# ADC.net
KiCad netlist of a schematic drawn in Altium Designer
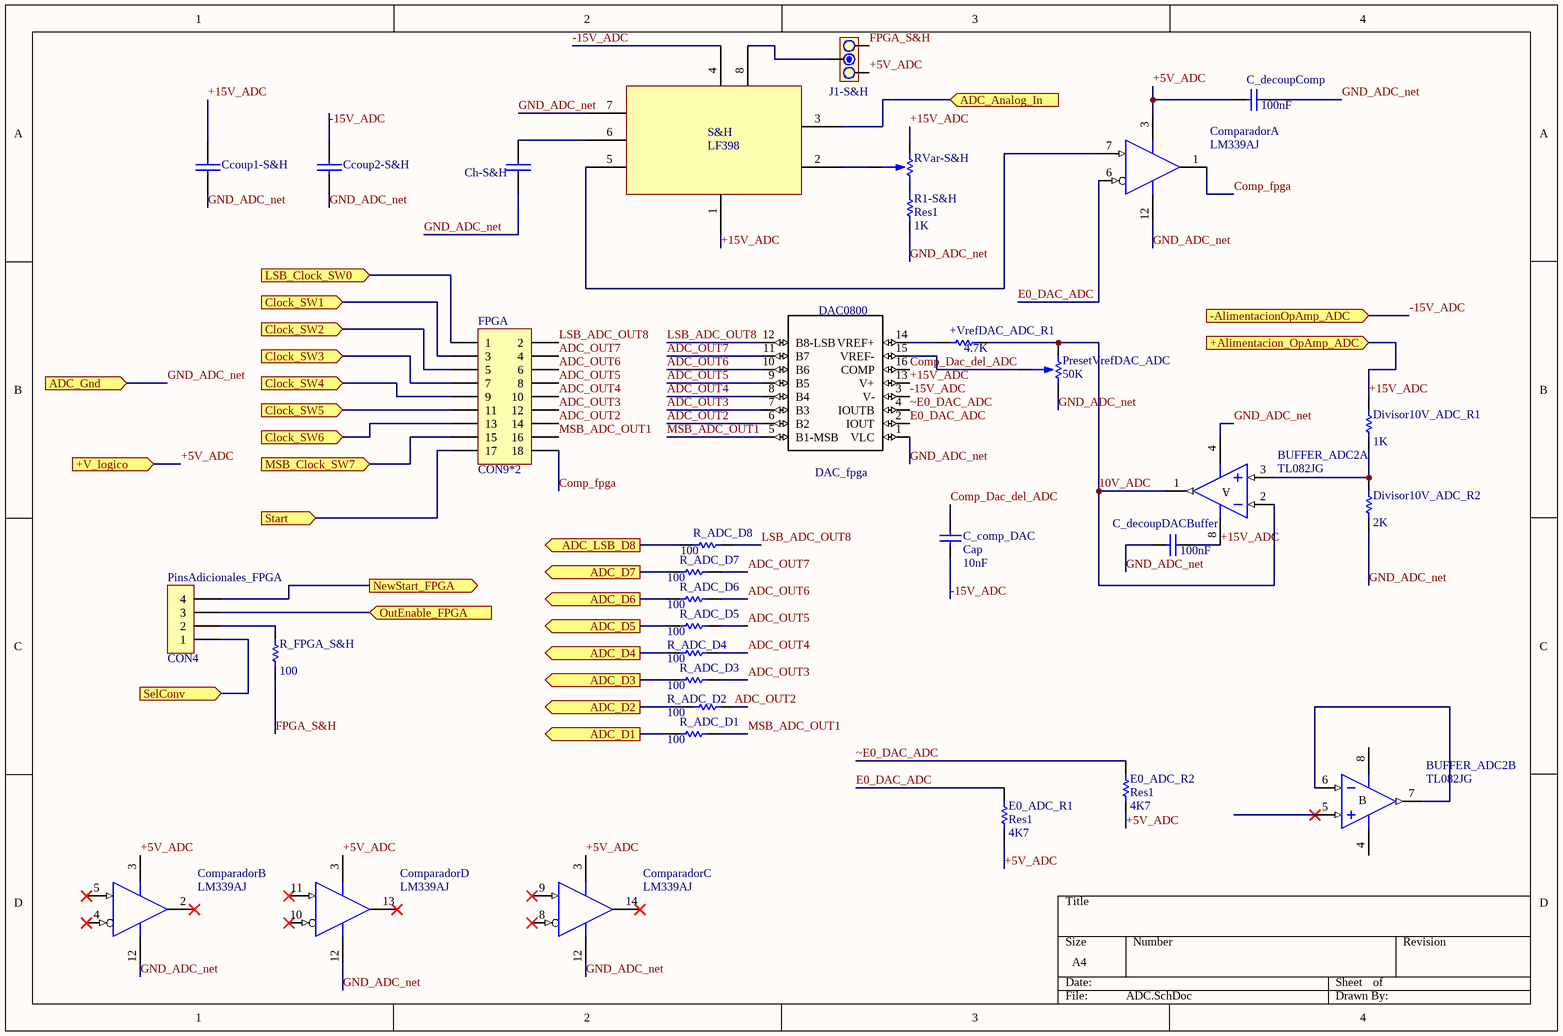
[diagram p0: ADC.SchDoc]

(export (version "E")
  (design (tool "Eeschema 10.0.6"))
  (components
    (comp (ref "+VrefDAC_ADC_R1")
      (value "4.7K")
      (footprint "AXIAL-0.3")
      (description "Resistor")
      (fields (field (name "Comment") "Res1") (field (name "PUBLISHER") "Altium Limited"))
      (libsource (lib "Miscellaneous Devices") (part "Res1"))
    )
    (comp (ref "BUFFER_ADC2")
      (value "TL082JG")
      (footprint "JG008")
      (description "JFET-Input Operational Amplifier")
      (fields (field (name "PUBLISHER") "Altium Limited"))
      (libsource (lib "TI Operational Amplifier") (part "TL082JG"))
    )
    (comp (ref "Ccoup1-S&H") (value "CAP") (footprint "CAP200") (libsource (lib "LIBEBAL") (part "CAP")))
    (comp (ref "Ccoup2-S&H") (value "CAP") (footprint "CAP200") (libsource (lib "LIBEBAL") (part "CAP")))
    (comp (ref "Ch-S&H") (value "CAP") (footprint "CAP200") (libsource (lib "LIBEBAL") (part "CAP")))
    (comp (ref "Comparador")
      (value "LM339AJ")
      (footprint "J014")
      (description "Quad Differential Comparator")
      (fields (field (name "PUBLISHER") "Altium Limited"))
      (libsource (lib "TI Analog Comparator") (part "LM339AJ"))
    )
    (comp (ref "C_comp_DAC")
      (value "Cap")
      (footprint "RAD-0.3")
      (description "Capacitor")
      (fields (field (name "ALTIUM_VALUE") "10nF") (field (name "PUBLISHER") "Altium Limited"))
      (libsource (lib "Miscellaneous Devices") (part "Cap"))
    )
    (comp (ref "C_decoupComp")
      (value "100nF")
      (footprint "RAD-0.3")
      (description "Capacitor")
      (fields (field (name "Comment") "Cap") (field (name "PUBLISHER") "Altium Limited"))
      (libsource (lib "Miscellaneous Devices") (part "Cap"))
    )
    (comp (ref "C_decoupDACBuffer")
      (value "100nF")
      (footprint "RAD-0.3")
      (description "Capacitor")
      (fields (field (name "Comment") "Cap") (field (name "PUBLISHER") "Altium Limited"))
      (libsource (lib "Miscellaneous Devices") (part "Cap"))
    )
    (comp (ref "DAC_fpga")
      (value "DAC0800")
      (footprint "*DIL16")
      (fields
        (field (name "MF") "Texas Instruments")
        (field (name "DIGI-KEY_PART_NUMBER") "DAC0800LCN/NOPB-ND")
      )
      (libsource (lib "DAC0800") (part "DAC0800"))
    )
    (comp (ref "Divisor10V_ADC_R1")
      (value "1K")
      (footprint "AXIAL-0.3")
      (description "Resistor")
      (fields (field (name "Comment") "Res1") (field (name "PUBLISHER") "Altium Limited"))
      (libsource (lib "Miscellaneous Devices") (part "Res1"))
    )
    (comp (ref "Divisor10V_ADC_R2")
      (value "2K")
      (footprint "AXIAL-0.3")
      (description "Resistor")
      (fields (field (name "Comment") "Res1") (field (name "PUBLISHER") "Altium Limited"))
      (libsource (lib "Miscellaneous Devices") (part "Res1"))
    )
    (comp (ref "E0_ADC_R1")
      (value "Res1")
      (footprint "AXIAL-0.3")
      (description "Resistor")
      (fields (field (name "ALTIUM_VALUE") "4K7") (field (name "PUBLISHER") "Altium Limited"))
      (libsource (lib "Miscellaneous Devices") (part "Res1"))
    )
    (comp (ref "E0_ADC_R2")
      (value "Res1")
      (footprint "AXIAL-0.3")
      (description "Resistor")
      (fields (field (name "ALTIUM_VALUE") "4K7") (field (name "PUBLISHER") "Altium Limited"))
      (libsource (lib "Miscellaneous Devices") (part "Res1"))
    )
    (comp (ref "FPGA") (value "CON9*2") (footprint "SIP9*2") (libsource (lib "LIBEBAL") (part "CON9*2")))
    (comp (ref "J1-S&H") (value "JUMPER") (footprint "JUMPER3") (libsource (lib "LIBEBAL") (part "JUMPER3")))
    (comp (ref "PinsAdicionales_FPGA")
      (value "CON4")
      (footprint "SIP4")
      (libsource (lib "LIBEBAL") (part "CON4"))
    )
    (comp (ref "PresetVrefDAC_ADC")
      (value "50K")
      (footprint "PRESET V")
      (libsource (lib "LIBEBAL") (part "PRESET"))
    )
    (comp (ref "R1-S&H")
      (value "Res1")
      (footprint "AXIAL-0.3")
      (description "Resistor")
      (fields (field (name "ALTIUM_VALUE") "1K") (field (name "PUBLISHER") "Altium Limited"))
      (libsource (lib "Miscellaneous Devices") (part "Res1"))
    )
    (comp (ref "RVar-S&H")
      (value "PRESET")
      (footprint "PRESET V")
      (libsource (lib "LIBEBAL") (part "PRESET"))
    )
    (comp (ref "R_ADC_D1")
      (value "100")
      (footprint "AXIAL-0.3")
      (description "Resistor")
      (fields (field (name "Comment") "Res1") (field (name "PUBLISHER") "Altium Limited"))
      (libsource (lib "Miscellaneous Devices") (part "Res1"))
    )
    (comp (ref "R_ADC_D2")
      (value "100")
      (footprint "AXIAL-0.3")
      (description "Resistor")
      (fields (field (name "Comment") "Res1") (field (name "PUBLISHER") "Altium Limited"))
      (libsource (lib "Miscellaneous Devices") (part "Res1"))
    )
    (comp (ref "R_ADC_D3")
      (value "100")
      (footprint "AXIAL-0.3")
      (description "Resistor")
      (fields (field (name "Comment") "Res1") (field (name "PUBLISHER") "Altium Limited"))
      (libsource (lib "Miscellaneous Devices") (part "Res1"))
    )
    (comp (ref "R_ADC_D4")
      (value "100")
      (footprint "AXIAL-0.3")
      (description "Resistor")
      (fields (field (name "Comment") "Res1") (field (name "PUBLISHER") "Altium Limited"))
      (libsource (lib "Miscellaneous Devices") (part "Res1"))
    )
    (comp (ref "R_ADC_D5")
      (value "100")
      (footprint "AXIAL-0.3")
      (description "Resistor")
      (fields (field (name "Comment") "Res1") (field (name "PUBLISHER") "Altium Limited"))
      (libsource (lib "Miscellaneous Devices") (part "Res1"))
    )
    (comp (ref "R_ADC_D6")
      (value "100")
      (footprint "AXIAL-0.3")
      (description "Resistor")
      (fields (field (name "Comment") "Res1") (field (name "PUBLISHER") "Altium Limited"))
      (libsource (lib "Miscellaneous Devices") (part "Res1"))
    )
    (comp (ref "R_ADC_D7")
      (value "100")
      (footprint "AXIAL-0.3")
      (description "Resistor")
      (fields (field (name "Comment") "Res1") (field (name "PUBLISHER") "Altium Limited"))
      (libsource (lib "Miscellaneous Devices") (part "Res1"))
    )
    (comp (ref "R_ADC_D8")
      (value "100")
      (footprint "AXIAL-0.3")
      (description "Resistor")
      (fields (field (name "Comment") "Res1") (field (name "PUBLISHER") "Altium Limited"))
      (libsource (lib "Miscellaneous Devices") (part "Res1"))
    )
    (comp (ref "R_FPGA_S&H")
      (value "100")
      (footprint "AXIAL-0.3")
      (description "Resistor")
      (fields (field (name "Comment") "Res1") (field (name "PUBLISHER") "Altium Limited"))
      (libsource (lib "Miscellaneous Devices") (part "Res1"))
    )
    (comp (ref "S&H")
      (value "LF398")
      (footprint "DIP8")
      (description "Sample and Hold Amplifier")
      (libsource (lib "LIBEBAL") (part "LM555"))
    )
  )
  (nets
    (net (code "1") (name "/+5V_ADC") (class "Default")
      (node (ref "C_decoupComp") (pin "1") (pinfunction "1_1") (pintype "passive"))
      (node (ref "Comparador") (pin "3") (pinfunction "VCC_3") (pintype "power_in"))
      (node (ref "E0_ADC_R1") (pin "1") (pinfunction "1_1") (pintype "passive"))
      (node (ref "E0_ADC_R2") (pin "1") (pinfunction "1_1") (pintype "passive"))
      (node (ref "J1-S&H") (pin "3") (pinfunction "3_3") (pintype "passive"))
    )
    (net (code "2") (name "/+15V_ADC") (class "Default")
      (node (ref "BUFFER_ADC2") (pin "8") (pinfunction "V+_8") (pintype "power_in"))
      (node (ref "C_decoupDACBuffer") (pin "2") (pinfunction "2_2") (pintype "passive"))
      (node (ref "Ccoup1-S&H") (pin "1") (pinfunction "1_1") (pintype "passive"))
      (node (ref "DAC_fpga") (pin "13") (pinfunction "V+_13") (pintype "bidirectional"))
      (node (ref "Divisor10V_ADC_R1") (pin "2") (pinfunction "2_2") (pintype "passive"))
      (node (ref "RVar-S&H") (pin "3") (pinfunction "3_3") (pintype "passive"))
      (node (ref "S&H") (pin "1") (pinfunction "GND_1") (pintype "passive"))
    )
    (net (code "3") (name "/-15V_ADC") (class "Default")
      (node (ref "C_comp_DAC") (pin "1") (pinfunction "1_1") (pintype "passive"))
      (node (ref "Ccoup2-S&H") (pin "1") (pinfunction "1_1") (pintype "passive"))
      (node (ref "DAC_fpga") (pin "3") (pinfunction "V-_3") (pintype "bidirectional"))
      (node (ref "S&H") (pin "4") (pinfunction "RESET_4") (pintype "passive"))
    )
    (net (code "4") (name "/10V_ADC") (class "Default")
      (node (ref "+VrefDAC_ADC_R1") (pin "2") (pinfunction "2_2") (pintype "passive"))
      (node (ref "BUFFER_ADC2") (pin "1") (pinfunction "OUT_1") (pintype "output"))
      (node (ref "BUFFER_ADC2") (pin "2") (pinfunction "IN-_2") (pintype "input"))
      (node (ref "PresetVrefDAC_ADC") (pin "3") (pinfunction "3_3") (pintype "passive"))
    )
    (net (code "5") (name "/ADC_Analog_In") (class "Default")
      (node (ref "S&H") (pin "3") (pinfunction "OUT_3") (pintype "passive"))
    )
    (net (code "6") (name "/ADC_D1") (class "Default")
      (node (ref "R_ADC_D1") (pin "1") (pinfunction "1_1") (pintype "passive"))
    )
    (net (code "7") (name "/ADC_D2") (class "Default")
      (node (ref "R_ADC_D2") (pin "1") (pinfunction "1_1") (pintype "passive"))
    )
    (net (code "8") (name "/ADC_D3") (class "Default")
      (node (ref "R_ADC_D3") (pin "1") (pinfunction "1_1") (pintype "passive"))
    )
    (net (code "9") (name "/ADC_D4") (class "Default")
      (node (ref "R_ADC_D4") (pin "1") (pinfunction "1_1") (pintype "passive"))
    )
    (net (code "10") (name "/ADC_D5") (class "Default")
      (node (ref "R_ADC_D5") (pin "1") (pinfunction "1_1") (pintype "passive"))
    )
    (net (code "11") (name "/ADC_D6") (class "Default")
      (node (ref "R_ADC_D6") (pin "1") (pinfunction "1_1") (pintype "passive"))
    )
    (net (code "12") (name "/ADC_D7") (class "Default")
      (node (ref "R_ADC_D7") (pin "1") (pinfunction "1_1") (pintype "passive"))
    )
    (net (code "13") (name "/ADC_LSB_D8") (class "Default")
      (node (ref "R_ADC_D8") (pin "1") (pinfunction "1_1") (pintype "passive"))
    )
    (net (code "14") (name "/ADC_OUT2") (class "Default")
      (node (ref "DAC_fpga") (pin "6") (pinfunction "B2_6") (pintype "bidirectional"))
      (node (ref "FPGA") (pin "14") (pinfunction "14_14") (pintype "passive"))
      (node (ref "R_ADC_D2") (pin "2") (pinfunction "2_2") (pintype "passive"))
    )
    (net (code "15") (name "/ADC_OUT3") (class "Default")
      (node (ref "DAC_fpga") (pin "7") (pinfunction "B3_7") (pintype "bidirectional"))
      (node (ref "FPGA") (pin "12") (pinfunction "12_12") (pintype "passive"))
      (node (ref "R_ADC_D3") (pin "2") (pinfunction "2_2") (pintype "passive"))
    )
    (net (code "16") (name "/ADC_OUT4") (class "Default")
      (node (ref "DAC_fpga") (pin "8") (pinfunction "B4_8") (pintype "bidirectional"))
      (node (ref "FPGA") (pin "10") (pinfunction "10_10") (pintype "passive"))
      (node (ref "R_ADC_D4") (pin "2") (pinfunction "2_2") (pintype "passive"))
    )
    (net (code "17") (name "/ADC_OUT5") (class "Default")
      (node (ref "DAC_fpga") (pin "9") (pinfunction "B5_9") (pintype "bidirectional"))
      (node (ref "FPGA") (pin "8") (pinfunction "8_8") (pintype "passive"))
      (node (ref "R_ADC_D5") (pin "2") (pinfunction "2_2") (pintype "passive"))
    )
    (net (code "18") (name "/ADC_OUT6") (class "Default")
      (node (ref "DAC_fpga") (pin "10") (pinfunction "B6_10") (pintype "bidirectional"))
      (node (ref "FPGA") (pin "6") (pinfunction "6_6") (pintype "passive"))
      (node (ref "R_ADC_D6") (pin "2") (pinfunction "2_2") (pintype "passive"))
    )
    (net (code "19") (name "/ADC_OUT7") (class "Default")
      (node (ref "DAC_fpga") (pin "11") (pinfunction "B7_11") (pintype "bidirectional"))
      (node (ref "FPGA") (pin "4") (pinfunction "4_4") (pintype "passive"))
      (node (ref "R_ADC_D7") (pin "2") (pinfunction "2_2") (pintype "passive"))
    )
    (net (code "20") (name "/Clock_SW1") (class "Default")
      (node (ref "FPGA") (pin "3") (pinfunction "3_3") (pintype "passive"))
    )
    (net (code "21") (name "/Clock_SW2") (class "Default")
      (node (ref "FPGA") (pin "5") (pinfunction "5_5") (pintype "passive"))
    )
    (net (code "22") (name "/Clock_SW3") (class "Default")
      (node (ref "FPGA") (pin "7") (pinfunction "7_7") (pintype "passive"))
    )
    (net (code "23") (name "/Clock_SW4") (class "Default")
      (node (ref "FPGA") (pin "9") (pinfunction "9_9") (pintype "passive"))
    )
    (net (code "24") (name "/Clock_SW5") (class "Default")
      (node (ref "FPGA") (pin "11") (pinfunction "11_11") (pintype "passive"))
    )
    (net (code "25") (name "/Clock_SW6") (class "Default")
      (node (ref "FPGA") (pin "13") (pinfunction "13_13") (pintype "passive"))
    )
    (net (code "26") (name "/Comp_Dac_del_ADC") (class "Default")
      (node (ref "C_comp_DAC") (pin "2") (pinfunction "2_2") (pintype "passive"))
      (node (ref "DAC_fpga") (pin "16") (pinfunction "COMP_16") (pintype "bidirectional"))
    )
    (net (code "27") (name "/Comp_fpga") (class "Default")
      (node (ref "Comparador") (pin "1") (pinfunction "OUT_1") (pintype "open_collector"))
      (node (ref "FPGA") (pin "18") (pinfunction "18_18") (pintype "passive"))
    )
    (net (code "28") (name "/E0_DAC_ADC") (class "Default")
      (node (ref "Comparador") (pin "6") (pinfunction "IN-_6") (pintype "input"))
      (node (ref "DAC_fpga") (pin "2") (pinfunction "IOUT_2") (pintype "bidirectional"))
      (node (ref "E0_ADC_R1") (pin "2") (pinfunction "2_2") (pintype "passive"))
    )
    (net (code "29") (name "/FPGA_S&H") (class "Default")
      (node (ref "J1-S&H") (pin "1") (pinfunction "1_1") (pintype "passive"))
      (node (ref "R_FPGA_S&H") (pin "1") (pinfunction "1_1") (pintype "passive"))
    )
    (net (code "30") (name "/GND_ADC_net") (class "Default")
      (node (ref "BUFFER_ADC2") (pin "4") (pinfunction "V-_4") (pintype "power_in"))
      (node (ref "C_decoupComp") (pin "2") (pinfunction "2_2") (pintype "passive"))
      (node (ref "C_decoupDACBuffer") (pin "1") (pinfunction "1_1") (pintype "passive"))
      (node (ref "Ccoup1-S&H") (pin "2") (pinfunction "2_2") (pintype "passive"))
      (node (ref "Ccoup2-S&H") (pin "2") (pinfunction "2_2") (pintype "passive"))
      (node (ref "Ch-S&H") (pin "2") (pinfunction "2_2") (pintype "passive"))
      (node (ref "Comparador") (pin "12") (pinfunction "GND_12") (pintype "power_in"))
      (node (ref "DAC_fpga") (pin "1") (pinfunction "VLC_1") (pintype "bidirectional"))
      (node (ref "Divisor10V_ADC_R2") (pin "1") (pinfunction "1_1") (pintype "passive"))
      (node (ref "PresetVrefDAC_ADC") (pin "1") (pinfunction "1_1") (pintype "passive"))
      (node (ref "R1-S&H") (pin "1") (pinfunction "1_1") (pintype "passive"))
      (node (ref "S&H") (pin "7") (pinfunction "DISCHARGE_7") (pintype "passive"))
    )
    (net (code "31") (name "/LSB_ADC_OUT8") (class "Default")
      (node (ref "DAC_fpga") (pin "12") (pinfunction "B8-LSB_12") (pintype "bidirectional"))
      (node (ref "FPGA") (pin "2") (pinfunction "2_2") (pintype "passive"))
      (node (ref "R_ADC_D8") (pin "2") (pinfunction "2_2") (pintype "passive"))
    )
    (net (code "32") (name "/LSB_Clock_SW0") (class "Default")
      (node (ref "FPGA") (pin "1") (pinfunction "1_1") (pintype "passive"))
    )
    (net (code "33") (name "/MSB_ADC_OUT1") (class "Default")
      (node (ref "DAC_fpga") (pin "5") (pinfunction "B1-MSB_5") (pintype "bidirectional"))
      (node (ref "FPGA") (pin "16") (pinfunction "16_16") (pintype "passive"))
      (node (ref "R_ADC_D1") (pin "2") (pinfunction "2_2") (pintype "passive"))
    )
    (net (code "34") (name "/MSB_Clock_SW7") (class "Default")
      (node (ref "FPGA") (pin "15") (pinfunction "15_15") (pintype "passive"))
    )
    (net (code "35") (name "/NewStart_FPGA") (class "Default")
      (node (ref "PinsAdicionales_FPGA") (pin "4") (pinfunction "4_4") (pintype "passive"))
    )
    (net (code "36") (name "/OutEnable_FPGA") (class "Default")
      (node (ref "PinsAdicionales_FPGA") (pin "3") (pinfunction "3_3") (pintype "passive"))
    )
    (net (code "37") (name "/SelConv") (class "Default")
      (node (ref "PinsAdicionales_FPGA") (pin "1") (pinfunction "1_1") (pintype "passive"))
    )
    (net (code "38") (name "/Start") (class "Default")
      (node (ref "FPGA") (pin "17") (pinfunction "17_17") (pintype "passive"))
    )
    (net (code "39") (name "/~E0_DAC_ADC") (class "Default")
      (node (ref "DAC_fpga") (pin "4") (pinfunction "IOUTB_4") (pintype "bidirectional"))
      (node (ref "E0_ADC_R2") (pin "2") (pinfunction "2_2") (pintype "passive"))
    )
    (net (code "40") (name "Net-(BUFFER_ADC2A-IN+)") (class "Default")
      (node (ref "BUFFER_ADC2") (pin "3") (pinfunction "IN+_3") (pintype "input"))
      (node (ref "Divisor10V_ADC_R1") (pin "1") (pinfunction "1_1") (pintype "passive"))
      (node (ref "Divisor10V_ADC_R2") (pin "2") (pinfunction "2_2") (pintype "passive"))
    )
    (net (code "41") (name "Net-(BUFFER_ADC2B-IN-)") (class "Default")
      (node (ref "BUFFER_ADC2") (pin "6") (pinfunction "IN-_6") (pintype "input"))
      (node (ref "BUFFER_ADC2") (pin "7") (pinfunction "OUT_7") (pintype "output"))
    )
    (net (code "42") (name "Net-(ComparadorA-IN+)") (class "Default")
      (node (ref "Comparador") (pin "7") (pinfunction "IN+_7") (pintype "input"))
      (node (ref "S&H") (pin "5") (pinfunction "C_VOLTAJE_5") (pintype "passive"))
    )
    (net (code "43") (name "Net-(DAC_fpga-VREF+)") (class "Default")
      (node (ref "+VrefDAC_ADC_R1") (pin "1") (pinfunction "1_1") (pintype "passive"))
      (node (ref "DAC_fpga") (pin "14") (pinfunction "VREF+_14") (pintype "bidirectional"))
    )
    (net (code "44") (name "Net-(DAC_fpga-VREF-)") (class "Default")
      (node (ref "DAC_fpga") (pin "15") (pinfunction "VREF-_15") (pintype "bidirectional"))
      (node (ref "PresetVrefDAC_ADC") (pin "2") (pinfunction "2_2") (pintype "passive"))
    )
    (net (code "45") (name "Net-(PinsAdicionales_FPGA-Pad2)") (class "Default")
      (node (ref "PinsAdicionales_FPGA") (pin "2") (pinfunction "2_2") (pintype "passive"))
      (node (ref "R_FPGA_S&H") (pin "2") (pinfunction "2_2") (pintype "passive"))
    )
    (net (code "46") (name "Net-(R1-S&H-Pad2)") (class "Default")
      (node (ref "R1-S&H") (pin "2") (pinfunction "2_2") (pintype "passive"))
      (node (ref "RVar-S&H") (pin "1") (pinfunction "1_1") (pintype "passive"))
    )
    (net (code "47") (name "Net-(S&H-THRESHOLD)") (class "Default")
      (node (ref "Ch-S&H") (pin "1") (pinfunction "1_1") (pintype "passive"))
      (node (ref "S&H") (pin "6") (pinfunction "THRESHOLD_6") (pintype "passive"))
    )
    (net (code "48") (name "Net-(S&H-TRIGGER)") (class "Default")
      (node (ref "RVar-S&H") (pin "2") (pinfunction "2_2") (pintype "passive"))
      (node (ref "S&H") (pin "2") (pinfunction "TRIGGER_2") (pintype "passive"))
    )
    (net (code "49") (name "Net-(S&H-VCC)") (class "Default")
      (node (ref "J1-S&H") (pin "2") (pinfunction "2_2") (pintype "passive"))
      (node (ref "S&H") (pin "8") (pinfunction "VCC_8") (pintype "passive"))
    )
    (net (code "50") (name "unconnected-(BUFFER_ADC2B-IN+-Pad5)") (class "Default")
      (node (ref "BUFFER_ADC2") (pin "5") (pinfunction "IN+_5") (pintype "input+no_connect"))
    )
    (net (code "51") (name "unconnected-(BUFFER_ADC2B-V+-Pad8)") (class "Default")
      (node (ref "BUFFER_ADC2") (pin "8") (pinfunction "V+_8") (pintype "power_in"))
    )
    (net (code "52") (name "unconnected-(BUFFER_ADC2B-V--Pad4)") (class "Default")
      (node (ref "BUFFER_ADC2") (pin "4") (pinfunction "V-_4") (pintype "power_in"))
    )
    (net (code "53") (name "unconnected-(ComparadorB-IN+-Pad5)") (class "Default")
      (node (ref "Comparador") (pin "5") (pinfunction "IN+_5") (pintype "input+no_connect"))
    )
    (net (code "54") (name "unconnected-(ComparadorB-IN--Pad4)") (class "Default")
      (node (ref "Comparador") (pin "4") (pinfunction "IN-_4") (pintype "input+no_connect"))
    )
    (net (code "55") (name "unconnected-(ComparadorB-OUT-Pad2)") (class "Default")
      (node (ref "Comparador") (pin "2") (pinfunction "OUT_2") (pintype "open_collector+no_connect"))
    )
    (net (code "56") (name "unconnected-(ComparadorC-IN+-Pad9)") (class "Default")
      (node (ref "Comparador") (pin "9") (pinfunction "IN+_9") (pintype "input+no_connect"))
    )
    (net (code "57") (name "unconnected-(ComparadorC-IN--Pad8)") (class "Default")
      (node (ref "Comparador") (pin "8") (pinfunction "IN-_8") (pintype "input+no_connect"))
    )
    (net (code "58") (name "unconnected-(ComparadorC-OUT-Pad14)") (class "Default")
      (node (ref "Comparador") (pin "14") (pinfunction "OUT_14") (pintype "open_collector+no_connect"))
    )
    (net (code "59") (name "unconnected-(ComparadorD-IN+-Pad11)") (class "Default")
      (node (ref "Comparador") (pin "11") (pinfunction "IN+_11") (pintype "input+no_connect"))
    )
    (net (code "60") (name "unconnected-(ComparadorD-IN--Pad10)") (class "Default")
      (node (ref "Comparador") (pin "10") (pinfunction "IN-_10") (pintype "input+no_connect"))
    )
    (net (code "61") (name "unconnected-(ComparadorD-OUT-Pad13)") (class "Default")
      (node (ref "Comparador") (pin "13") (pinfunction "OUT_13") (pintype "open_collector+no_connect"))
    )
  )
)
